# CC1101Adapter_V1_00.net
KiCad netlist of a schematic drawn in EAGLE
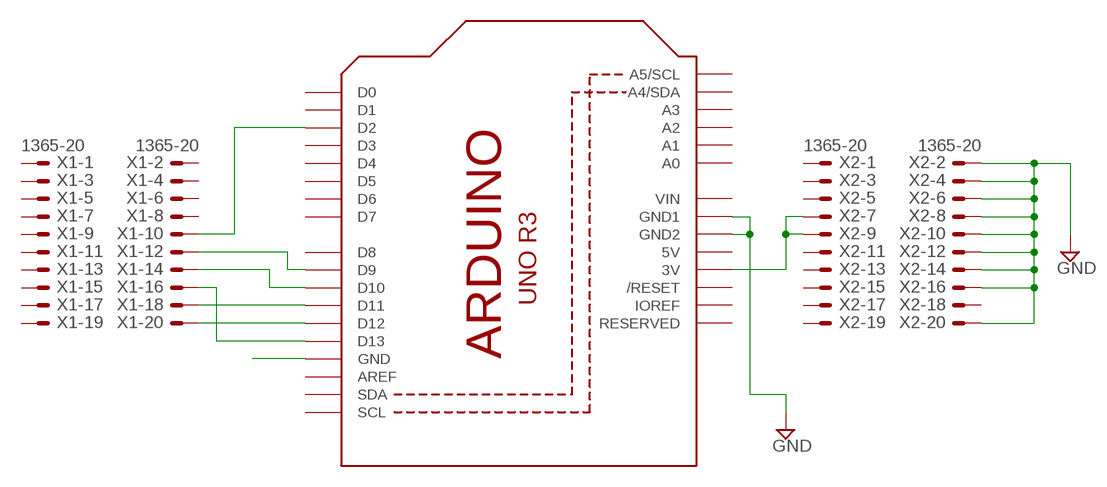
[diagram p0: schematic, sheet 1]

(export (version "E")
  (design (tool "Eeschema 10.0.6"))
  (components
    (comp (ref "U1")
      (value "ARDUINOR3-DIMENSION")
      (footprint "eagle-import:ARDUINOR3")
      (libsource (lib "eagle-import") (part "ARDUINOR3-DIMENSION"))
    )
    (comp (ref "X1")
      (value "1365-20")
      (footprint "eagle-import:1365-20")
      (libsource (lib "eagle-import") (part "1365-20"))
    )
    (comp (ref "X2")
      (value "1365-20")
      (footprint "eagle-import:1365-20")
      (libsource (lib "eagle-import") (part "1365-20"))
    )
  )
  (nets
    (net (code "1") (name "/5V") (class "Default")
      (node (ref "U1") (pin "5V") (pinfunction "5V_5V") (pintype "power_in"))
    )
    (net (code "2") (name "/VIN") (class "Default")
      (node (ref "U1") (pin "VIN") (pinfunction "VIN_VIN") (pintype "power_in"))
    )
    (net (code "3") (name "GND") (class "Default")
      (node (ref "U1") (pin "GND1") (pinfunction "GND1_GND1") (pintype "power_in"))
      (node (ref "U1") (pin "GND2") (pinfunction "GND2_GND2") (pintype "power_in"))
      (node (ref "X2") (pin "10") (pinfunction "S_10") (pintype "passive"))
      (node (ref "X2") (pin "12") (pinfunction "S_12") (pintype "passive"))
      (node (ref "X2") (pin "14") (pinfunction "S_14") (pintype "passive"))
      (node (ref "X2") (pin "16") (pinfunction "S_16") (pintype "passive"))
      (node (ref "X2") (pin "2") (pinfunction "S_2") (pintype "passive"))
      (node (ref "X2") (pin "20") (pinfunction "S_20") (pintype "passive"))
      (node (ref "X2") (pin "4") (pinfunction "S_4") (pintype "passive"))
      (node (ref "X2") (pin "6") (pinfunction "S_6") (pintype "passive"))
      (node (ref "X2") (pin "8") (pinfunction "S_8") (pintype "passive"))
    )
    (net (code "4") (name "Net-(X1B-S)") (class "Default")
      (node (ref "U1") (pin "D2") (pinfunction "D2_D2") (pintype "bidirectional"))
      (node (ref "X1") (pin "10") (pinfunction "S_10") (pintype "passive"))
    )
    (net (code "5") (name "Net-(X1D-S)") (class "Default")
      (node (ref "U1") (pin "D9") (pinfunction "D9_D9") (pintype "bidirectional"))
      (node (ref "X1") (pin "12") (pinfunction "S_12") (pintype "passive"))
    )
    (net (code "6") (name "Net-(X1F-S)") (class "Default")
      (node (ref "U1") (pin "D10") (pinfunction "D10_D10") (pintype "bidirectional"))
      (node (ref "X1") (pin "14") (pinfunction "S_14") (pintype "passive"))
    )
    (net (code "7") (name "Net-(X1H-S)") (class "Default")
      (node (ref "U1") (pin "D13") (pinfunction "D13_D13") (pintype "bidirectional"))
      (node (ref "X1") (pin "16") (pinfunction "S_16") (pintype "passive"))
    )
    (net (code "8") (name "Net-(X1J-S)") (class "Default")
      (node (ref "U1") (pin "D11") (pinfunction "D11_D11") (pintype "bidirectional"))
      (node (ref "X1") (pin "18") (pinfunction "S_18") (pintype "passive"))
    )
    (net (code "9") (name "Net-(X1M-S)") (class "Default")
      (node (ref "U1") (pin "D12") (pinfunction "D12_D12") (pintype "bidirectional"))
      (node (ref "X1") (pin "20") (pinfunction "S_20") (pintype "passive"))
    )
    (net (code "10") (name "Net-(X2R-S)") (class "Default")
      (node (ref "U1") (pin "3V") (pinfunction "3V_3V") (pintype "power_in"))
      (node (ref "X2") (pin "7") (pinfunction "S_7") (pintype "passive"))
      (node (ref "X2") (pin "9") (pinfunction "S_9") (pintype "passive"))
    )
    (net (code "11") (name "unconnected-(U1-A4{slash}SDA-PadA4)") (class "Default")
      (node (ref "U1") (pin "A4") (pinfunction "A4/SDA_A4") (pintype "bidirectional"))
    )
    (net (code "12") (name "unconnected-(U1-A5{slash}SCL-PadA5)") (class "Default")
      (node (ref "U1") (pin "A5") (pinfunction "A5/SCL_A5") (pintype "bidirectional"))
    )
    (net (code "13") (name "unconnected-(U1-PadA0)") (class "Default")
      (node (ref "U1") (pin "A0") (pinfunction "A0_A0") (pintype "bidirectional"))
    )
    (net (code "14") (name "unconnected-(U1-PadA1)") (class "Default")
      (node (ref "U1") (pin "A1") (pinfunction "A1_A1") (pintype "bidirectional"))
    )
    (net (code "15") (name "unconnected-(U1-PadA2)") (class "Default")
      (node (ref "U1") (pin "A2") (pinfunction "A2_A2") (pintype "bidirectional"))
    )
    (net (code "16") (name "unconnected-(U1-PadA3)") (class "Default")
      (node (ref "U1") (pin "A3") (pinfunction "A3_A3") (pintype "bidirectional"))
    )
    (net (code "17") (name "unconnected-(U1-PadAREF)") (class "Default")
      (node (ref "U1") (pin "AREF") (pinfunction "AREF_AREF") (pintype "bidirectional"))
    )
    (net (code "18") (name "unconnected-(U1-PadD0)") (class "Default")
      (node (ref "U1") (pin "D0") (pinfunction "D0_D0") (pintype "bidirectional"))
    )
    (net (code "19") (name "unconnected-(U1-PadD1)") (class "Default")
      (node (ref "U1") (pin "D1") (pinfunction "D1_D1") (pintype "bidirectional"))
    )
    (net (code "20") (name "unconnected-(U1-PadD3)") (class "Default")
      (node (ref "U1") (pin "D3") (pinfunction "D3_D3") (pintype "bidirectional"))
    )
    (net (code "21") (name "unconnected-(U1-PadD4)") (class "Default")
      (node (ref "U1") (pin "D4") (pinfunction "D4_D4") (pintype "bidirectional"))
    )
    (net (code "22") (name "unconnected-(U1-PadD5)") (class "Default")
      (node (ref "U1") (pin "D5") (pinfunction "D5_D5") (pintype "bidirectional"))
    )
    (net (code "23") (name "unconnected-(U1-PadD6)") (class "Default")
      (node (ref "U1") (pin "D6") (pinfunction "D6_D6") (pintype "bidirectional"))
    )
    (net (code "24") (name "unconnected-(U1-PadD7)") (class "Default")
      (node (ref "U1") (pin "D7") (pinfunction "D7_D7") (pintype "bidirectional"))
    )
    (net (code "25") (name "unconnected-(U1-PadD8)") (class "Default")
      (node (ref "U1") (pin "D8") (pinfunction "D8_D8") (pintype "bidirectional"))
    )
    (net (code "26") (name "unconnected-(U1-PadGND)") (class "Default")
      (node (ref "U1") (pin "GND") (pinfunction "GND_GND") (pintype "power_in"))
    )
    (net (code "27") (name "unconnected-(U1-PadIOREF)") (class "Default")
      (node (ref "U1") (pin "IOREF") (pinfunction "IOREF_IOREF") (pintype "output"))
    )
    (net (code "28") (name "unconnected-(U1-PadRESERVED)") (class "Default")
      (node (ref "U1") (pin "RESERVED") (pinfunction "RESERVED_RESERVED") (pintype "no_connect"))
    )
    (net (code "29") (name "unconnected-(U1-PadSCL)") (class "Default")
      (node (ref "U1") (pin "SCL") (pinfunction "SCL_SCL") (pintype "bidirectional"))
    )
    (net (code "30") (name "unconnected-(U1-PadSDA)") (class "Default")
      (node (ref "U1") (pin "SDA") (pinfunction "SDA_SDA") (pintype "bidirectional"))
    )
    (net (code "31") (name "unconnected-(U1-{slash}RESET-PadRESET)") (class "Default")
      (node (ref "U1") (pin "RESET") (pinfunction "/RESET_RESET") (pintype "bidirectional"))
    )
    (net (code "32") (name "unconnected-(X1A-S-Pad1)") (class "Default")
      (node (ref "X1") (pin "1") (pinfunction "S_1") (pintype "passive"))
    )
    (net (code "33") (name "unconnected-(X1C-S-Pad11)") (class "Default")
      (node (ref "X1") (pin "11") (pinfunction "S_11") (pintype "passive"))
    )
    (net (code "34") (name "unconnected-(X1E-S-Pad13)") (class "Default")
      (node (ref "X1") (pin "13") (pinfunction "S_13") (pintype "passive"))
    )
    (net (code "35") (name "unconnected-(X1G-S-Pad15)") (class "Default")
      (node (ref "X1") (pin "15") (pinfunction "S_15") (pintype "passive"))
    )
    (net (code "36") (name "unconnected-(X1I-S-Pad17)") (class "Default")
      (node (ref "X1") (pin "17") (pinfunction "S_17") (pintype "passive"))
    )
    (net (code "37") (name "unconnected-(X1K-S-Pad19)") (class "Default")
      (node (ref "X1") (pin "19") (pinfunction "S_19") (pintype "passive"))
    )
    (net (code "38") (name "unconnected-(X1L-S-Pad2)") (class "Default")
      (node (ref "X1") (pin "2") (pinfunction "S_2") (pintype "passive"))
    )
    (net (code "39") (name "unconnected-(X1N-S-Pad3)") (class "Default")
      (node (ref "X1") (pin "3") (pinfunction "S_3") (pintype "passive"))
    )
    (net (code "40") (name "unconnected-(X1O-S-Pad4)") (class "Default")
      (node (ref "X1") (pin "4") (pinfunction "S_4") (pintype "passive"))
    )
    (net (code "41") (name "unconnected-(X1P-S-Pad5)") (class "Default")
      (node (ref "X1") (pin "5") (pinfunction "S_5") (pintype "passive"))
    )
    (net (code "42") (name "unconnected-(X1Q-S-Pad6)") (class "Default")
      (node (ref "X1") (pin "6") (pinfunction "S_6") (pintype "passive"))
    )
    (net (code "43") (name "unconnected-(X1R-S-Pad7)") (class "Default")
      (node (ref "X1") (pin "7") (pinfunction "S_7") (pintype "passive"))
    )
    (net (code "44") (name "unconnected-(X1S-S-Pad8)") (class "Default")
      (node (ref "X1") (pin "8") (pinfunction "S_8") (pintype "passive"))
    )
    (net (code "45") (name "unconnected-(X1T-S-Pad9)") (class "Default")
      (node (ref "X1") (pin "9") (pinfunction "S_9") (pintype "passive"))
    )
    (net (code "46") (name "unconnected-(X2A-S-Pad1)") (class "Default")
      (node (ref "X2") (pin "1") (pinfunction "S_1") (pintype "passive"))
    )
    (net (code "47") (name "unconnected-(X2C-S-Pad11)") (class "Default")
      (node (ref "X2") (pin "11") (pinfunction "S_11") (pintype "passive"))
    )
    (net (code "48") (name "unconnected-(X2E-S-Pad13)") (class "Default")
      (node (ref "X2") (pin "13") (pinfunction "S_13") (pintype "passive"))
    )
    (net (code "49") (name "unconnected-(X2G-S-Pad15)") (class "Default")
      (node (ref "X2") (pin "15") (pinfunction "S_15") (pintype "passive"))
    )
    (net (code "50") (name "unconnected-(X2I-S-Pad17)") (class "Default")
      (node (ref "X2") (pin "17") (pinfunction "S_17") (pintype "passive"))
    )
    (net (code "51") (name "unconnected-(X2J-S-Pad18)") (class "Default")
      (node (ref "X2") (pin "18") (pinfunction "S_18") (pintype "passive"))
    )
    (net (code "52") (name "unconnected-(X2K-S-Pad19)") (class "Default")
      (node (ref "X2") (pin "19") (pinfunction "S_19") (pintype "passive"))
    )
    (net (code "53") (name "unconnected-(X2N-S-Pad3)") (class "Default")
      (node (ref "X2") (pin "3") (pinfunction "S_3") (pintype "passive"))
    )
    (net (code "54") (name "unconnected-(X2P-S-Pad5)") (class "Default")
      (node (ref "X2") (pin "5") (pinfunction "S_5") (pintype "passive"))
    )
  )
)
